# hall.net
KiCad netlist of a schematic drawn in EAGLE
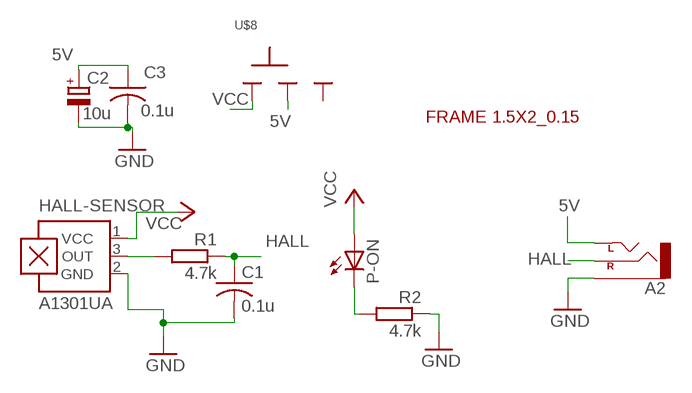
[diagram p0: schematic, sheet 1]

(export (version "E")
  (design (tool "Eeschema 10.0.6"))
  (components
    (comp (ref "A2")
      (value "AUX-CONNECTOR_CEDT_JANUARY_2015_V5_AUDIO-JACKPTH")
      (footprint "eagle-import:AUX-CONNECTOR_CEDT_JANUARY_2015_V5_AUDIO-JACK")
      (libsource (lib "eagle-import") (part "AUX-CONNECTOR_CEDT_JANUARY_2015_V5_AUDIO-JACKPTH"))
    )
    (comp (ref "C1")
      (value "0.1u")
      (footprint "eagle-import:C025-024X044")
      (libsource (lib "eagle-import") (part "C-US025-024X044"))
    )
    (comp (ref "C2")
      (value "10u")
      (footprint "eagle-import:E2,5-5")
      (libsource (lib "eagle-import") (part "CPOL-EUE2.5-5"))
    )
    (comp (ref "C3")
      (value "0.1u")
      (footprint "eagle-import:C025-024X044")
      (libsource (lib "eagle-import") (part "C-US025-024X044"))
    )
    (comp (ref "HALL-SENSOR")
      (value "A1301UA")
      (footprint "eagle-import:SIP3-UA")
      (fields (field (name "MF") "ALLEGRO MICROSYSTEMS, INC.") (field (name "MPN") "A1301EUA-T"))
      (libsource (lib "eagle-import") (part "A13?UA01"))
    )
    (comp (ref "P-ON")
      (value "LED3MM")
      (footprint "eagle-import:LED3MM")
      (libsource (lib "eagle-import") (part "LED3MM"))
    )
    (comp (ref "R1")
      (value "4.7k")
      (footprint "eagle-import:0204_7")
      (libsource (lib "eagle-import") (part "R-EU_0204/7"))
    )
    (comp (ref "R2")
      (value "4.7k")
      (footprint "eagle-import:0204_7")
      (libsource (lib "eagle-import") (part "R-EU_0204/7"))
    )
    (comp (ref "U$1")
      (value "FRAME_1.5X2_RAD_0.15")
      (footprint "eagle-import:FRAME_1.5X2_RAD_0.15")
      (libsource (lib "eagle-import") (part "FRAME_1.5X2_RAD_0.15"))
    )
    (comp (ref "U$8")
      (value "SLIDESWITCH-BIG")
      (footprint "eagle-import:BIGSWITCH")
      (libsource (lib "eagle-import") (part "SLIDESWITCH-BIG"))
    )
  )
  (nets
    (net (code "1") (name "/5V") (class "Default")
      (node (ref "A2") (pin "TIP") (pinfunction "LEFT_TIP") (pintype "bidirectional"))
      (node (ref "C2") (pin "+") (pinfunction "+_+") (pintype "passive"))
      (node (ref "C3") (pin "1") (pinfunction "1_1") (pintype "passive"))
      (node (ref "U$8") (pin "2") (pinfunction "2_2") (pintype "bidirectional"))
    )
    (net (code "2") (name "/HALL") (class "Default")
      (node (ref "A2") (pin "RING") (pinfunction "RIGHT_RING") (pintype "bidirectional"))
      (node (ref "C1") (pin "1") (pinfunction "1_1") (pintype "passive"))
      (node (ref "R1") (pin "1") (pinfunction "1_1") (pintype "passive"))
    )
    (net (code "3") (name "GND") (class "Default")
      (node (ref "A2") (pin "SLEEVE") (pinfunction "SLEEVE_SLEEVE") (pintype "bidirectional"))
      (node (ref "C1") (pin "2") (pinfunction "2_2") (pintype "passive"))
      (node (ref "C2") (pin "-") (pinfunction "-_-") (pintype "passive"))
      (node (ref "C3") (pin "2") (pinfunction "2_2") (pintype "passive"))
      (node (ref "HALL-SENSOR") (pin "2") (pinfunction "GND_2") (pintype "power_in"))
      (node (ref "R2") (pin "1") (pinfunction "1_1") (pintype "passive"))
    )
    (net (code "4") (name "Net-(HALL-SENSOR-OUT)") (class "Default")
      (node (ref "HALL-SENSOR") (pin "3") (pinfunction "OUT_3") (pintype "output"))
      (node (ref "R1") (pin "2") (pinfunction "2_2") (pintype "passive"))
    )
    (net (code "5") (name "Net-(P-ON-C)") (class "Default")
      (node (ref "P-ON") (pin "K") (pinfunction "C_K") (pintype "passive"))
      (node (ref "R2") (pin "2") (pinfunction "2_2") (pintype "passive"))
    )
    (net (code "6") (name "VCC") (class "Default")
      (node (ref "HALL-SENSOR") (pin "1") (pinfunction "VCC_1") (pintype "power_in"))
      (node (ref "P-ON") (pin "A") (pinfunction "A_A") (pintype "passive"))
      (node (ref "U$8") (pin "1") (pinfunction "1_1") (pintype "bidirectional"))
    )
    (net (code "7") (name "unconnected-(U$8-Pad3)") (class "Default")
      (node (ref "U$8") (pin "3") (pinfunction "3_3") (pintype "bidirectional"))
    )
  )
)
